# BrushlessDrive.net
KiCad netlist of a schematic drawn in Altium Designer
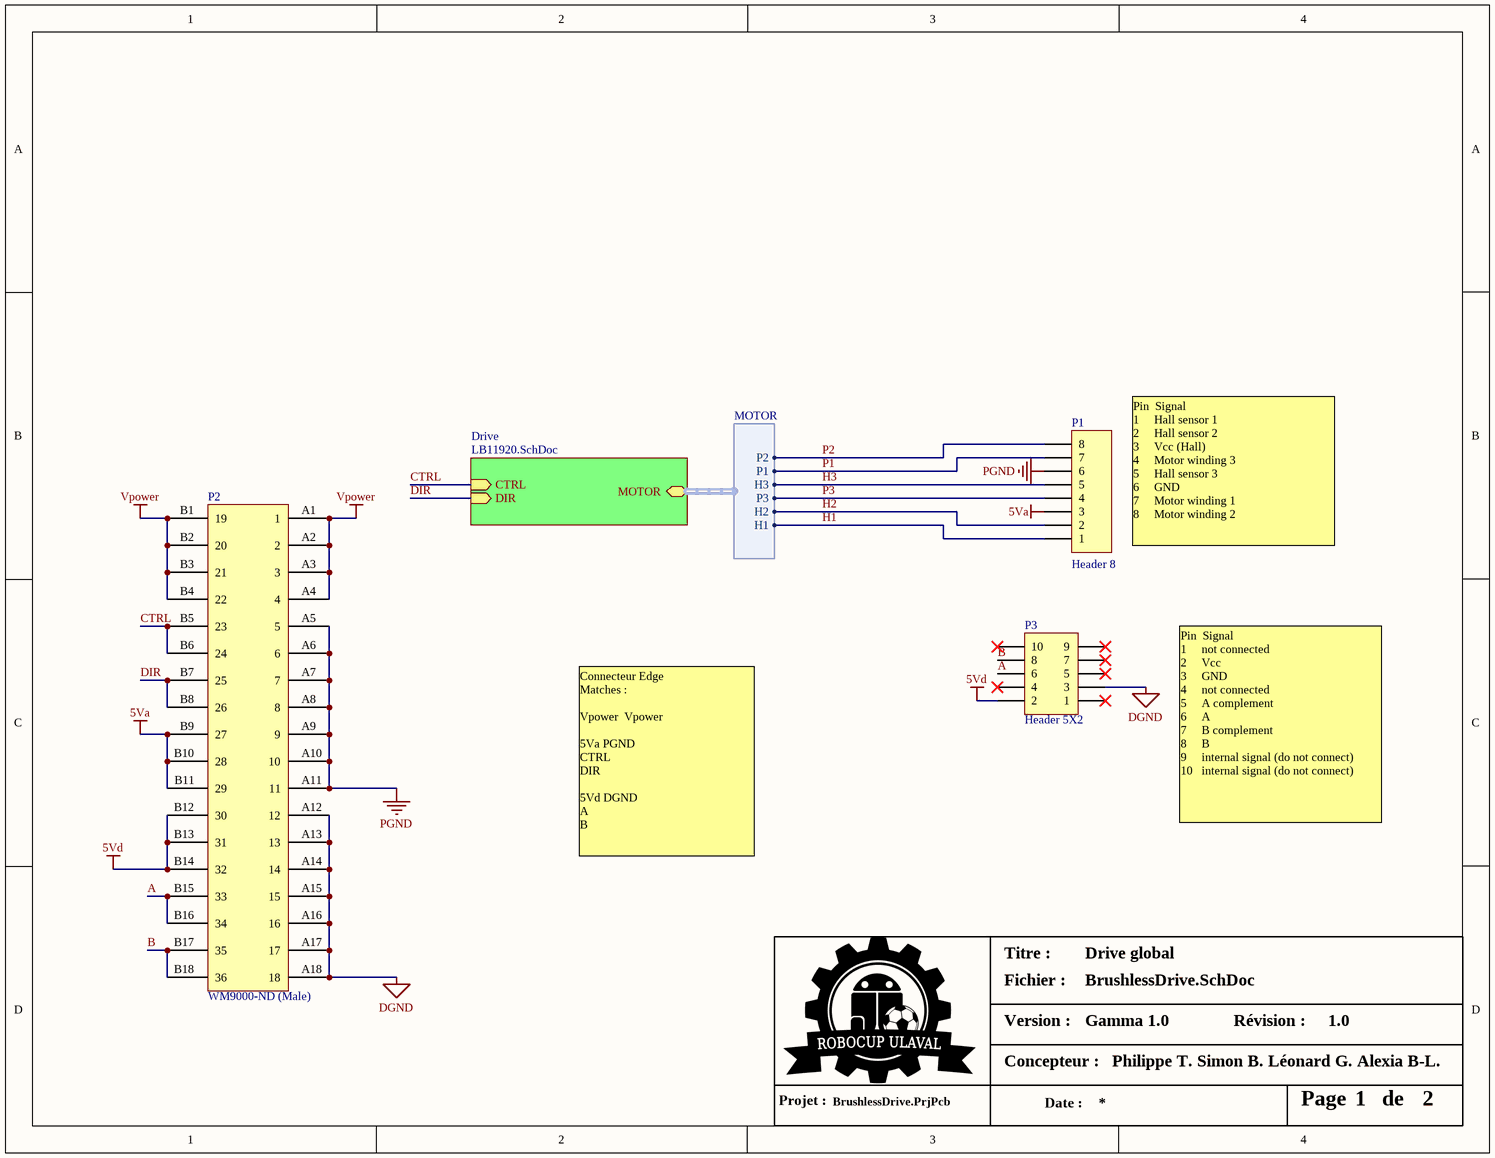
[diagram p0: BrushlessDrive.SchDoc]

(export (version "E")
  (design (tool "Eeschema 10.0.6"))
  (components
    (comp (ref "P1")
      (value "Header 8")
      (footprint "HallSensor Connector")
      (description "Header, 8-Pin")
      (fields (field (name "PUBLISHER") "Altium Limited"))
      (libsource (lib "Miscellaneous Connectors") (part "Header 8"))
    )
    (comp (ref "P2")
      (value "WM9000-ND (Male)")
      (footprint "Edge connector 36Pos")
      (libsource (lib "BrushlessDrive") (part "WM9000-ND (Male)"))
    )
    (comp (ref "P3")
      (value "Header 5X2")
      (footprint "Encoder Connector")
      (description "Header, 5-Pin, Dual row")
      (fields (field (name "PUBLISHER") "Altium Limited"))
      (libsource (lib "Miscellaneous Connectors") (part "Header 5X2"))
    )
  )
  (nets
    (net (code "2") (name "/A") (class "Default")
      (node (ref "P2") (pin "B15") (pinfunction "33_B15") (pintype "passive"))
      (node (ref "P2") (pin "B16") (pinfunction "34_B16") (pintype "passive"))
      (node (ref "P3") (pin "6") (pinfunction "6_6") (pintype "passive"))
    )
    (net (code "3") (name "/B") (class "Default")
      (node (ref "P2") (pin "B17") (pinfunction "35_B17") (pintype "passive"))
      (node (ref "P2") (pin "B18") (pinfunction "36_B18") (pintype "passive"))
      (node (ref "P3") (pin "8") (pinfunction "8_8") (pintype "passive"))
    )
    (net (code "4") (name "/CTRL") (class "Default")
      (node (ref "P2") (pin "B5") (pinfunction "23_B5") (pintype "passive"))
      (node (ref "P2") (pin "B6") (pinfunction "24_B6") (pintype "passive"))
    )
    (net (code "5") (name "/DIR") (class "Default")
      (node (ref "P2") (pin "B7") (pinfunction "25_B7") (pintype "passive"))
      (node (ref "P2") (pin "B8") (pinfunction "26_B8") (pintype "passive"))
    )
    (net (code "6") (name "/H1") (class "Default")
      (node (ref "P1") (pin "1") (pinfunction "1_1") (pintype "passive"))
    )
    (net (code "7") (name "/H2") (class "Default")
      (node (ref "P1") (pin "2") (pinfunction "2_2") (pintype "passive"))
    )
    (net (code "8") (name "/H3") (class "Default")
      (node (ref "P1") (pin "5") (pinfunction "5_5") (pintype "passive"))
    )
    (net (code "9") (name "/P1") (class "Default")
      (node (ref "P1") (pin "7") (pinfunction "7_7") (pintype "passive"))
    )
    (net (code "10") (name "/P2") (class "Default")
      (node (ref "P1") (pin "8") (pinfunction "8_8") (pintype "passive"))
    )
    (net (code "11") (name "/P3") (class "Default")
      (node (ref "P1") (pin "4") (pinfunction "4_4") (pintype "passive"))
    )
    (net (code "13") (name "5Va") (class "Default")
      (node (ref "P1") (pin "3") (pinfunction "3_3") (pintype "passive"))
      (node (ref "P2") (pin "B10") (pinfunction "28_B10") (pintype "passive"))
      (node (ref "P2") (pin "B11") (pinfunction "29_B11") (pintype "passive"))
      (node (ref "P2") (pin "B9") (pinfunction "27_B9") (pintype "passive"))
    )
    (net (code "14") (name "5Vd") (class "Default")
      (node (ref "P2") (pin "B12") (pinfunction "30_B12") (pintype "passive"))
      (node (ref "P2") (pin "B13") (pinfunction "31_B13") (pintype "passive"))
      (node (ref "P2") (pin "B14") (pinfunction "32_B14") (pintype "passive"))
      (node (ref "P3") (pin "2") (pinfunction "2_2") (pintype "passive"))
    )
    (net (code "15") (name "DGND") (class "Default")
      (node (ref "P2") (pin "A12") (pinfunction "12_A12") (pintype "passive"))
      (node (ref "P2") (pin "A13") (pinfunction "13_A13") (pintype "passive"))
      (node (ref "P2") (pin "A14") (pinfunction "14_A14") (pintype "passive"))
      (node (ref "P2") (pin "A15") (pinfunction "15_A15") (pintype "passive"))
      (node (ref "P2") (pin "A16") (pinfunction "16_A16") (pintype "passive"))
      (node (ref "P2") (pin "A17") (pinfunction "17_A17") (pintype "passive"))
      (node (ref "P2") (pin "A18") (pinfunction "18_A18") (pintype "passive"))
      (node (ref "P3") (pin "3") (pinfunction "3_3") (pintype "passive"))
    )
    (net (code "16") (name "PGND") (class "Default")
      (node (ref "P1") (pin "6") (pinfunction "6_6") (pintype "passive"))
      (node (ref "P2") (pin "A10") (pinfunction "10_A10") (pintype "passive"))
      (node (ref "P2") (pin "A11") (pinfunction "11_A11") (pintype "passive"))
      (node (ref "P2") (pin "A5") (pinfunction "5_A5") (pintype "passive"))
      (node (ref "P2") (pin "A6") (pinfunction "6_A6") (pintype "passive"))
      (node (ref "P2") (pin "A7") (pinfunction "7_A7") (pintype "passive"))
      (node (ref "P2") (pin "A8") (pinfunction "8_A8") (pintype "passive"))
      (node (ref "P2") (pin "A9") (pinfunction "9_A9") (pintype "passive"))
    )
    (net (code "17") (name "Vpower") (class "Default")
      (node (ref "P2") (pin "A1") (pinfunction "1_A1") (pintype "passive"))
      (node (ref "P2") (pin "A2") (pinfunction "2_A2") (pintype "passive"))
      (node (ref "P2") (pin "A3") (pinfunction "3_A3") (pintype "passive"))
      (node (ref "P2") (pin "A4") (pinfunction "4_A4") (pintype "passive"))
      (node (ref "P2") (pin "B1") (pinfunction "19_B1") (pintype "passive"))
      (node (ref "P2") (pin "B2") (pinfunction "20_B2") (pintype "passive"))
      (node (ref "P2") (pin "B3") (pinfunction "21_B3") (pintype "passive"))
      (node (ref "P2") (pin "B4") (pinfunction "22_B4") (pintype "passive"))
    )
    (net (code "18") (name "unconnected-(P3-Pad1)") (class "Default")
      (node (ref "P3") (pin "1") (pinfunction "1_1") (pintype "passive+no_connect"))
    )
    (net (code "19") (name "unconnected-(P3-Pad4)") (class "Default")
      (node (ref "P3") (pin "4") (pinfunction "4_4") (pintype "passive+no_connect"))
    )
    (net (code "20") (name "unconnected-(P3-Pad5)") (class "Default")
      (node (ref "P3") (pin "5") (pinfunction "5_5") (pintype "passive+no_connect"))
    )
    (net (code "21") (name "unconnected-(P3-Pad7)") (class "Default")
      (node (ref "P3") (pin "7") (pinfunction "7_7") (pintype "passive+no_connect"))
    )
    (net (code "22") (name "unconnected-(P3-Pad9)") (class "Default")
      (node (ref "P3") (pin "9") (pinfunction "9_9") (pintype "passive+no_connect"))
    )
    (net (code "23") (name "unconnected-(P3-Pad10)") (class "Default")
      (node (ref "P3") (pin "10") (pinfunction "10_10") (pintype "passive+no_connect"))
    )
  )
)
